# LaserLEDController.net
KiCad netlist of a schematic drawn in Altium Designer
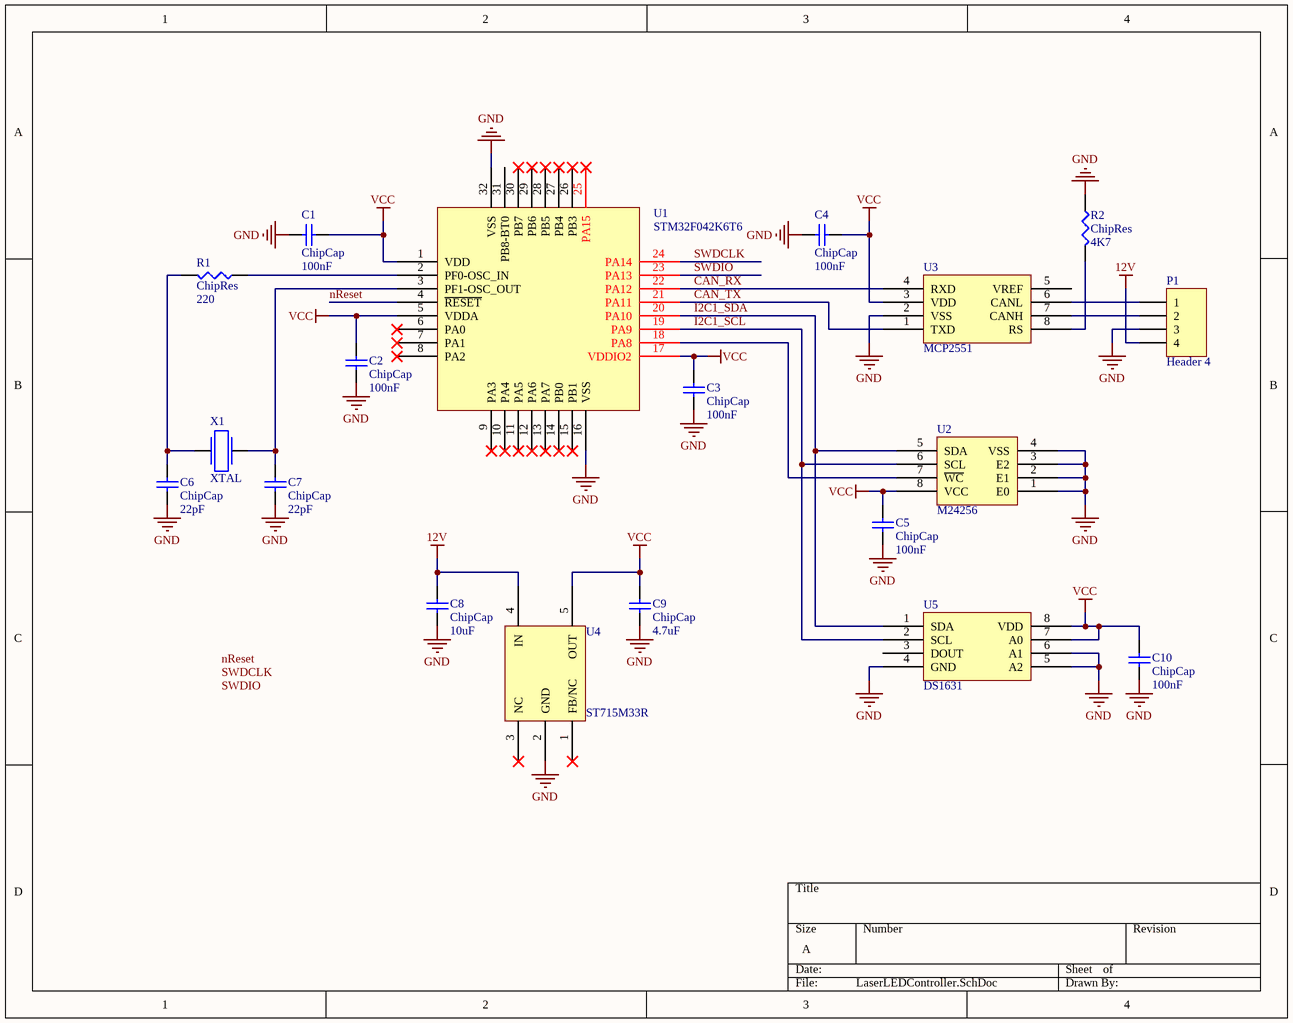
[diagram p0: LaserLEDController.SchDoc]

(export (version "E")
  (design (tool "Eeschema 10.0.6"))
  (components
    (comp (ref "C1")
      (value "ChipCap")
      (footprint "CAP0603")
      (description "Capacitor")
      (fields (field (name "ALTIUM_VALUE") "100nF") (field (name "PUBLISHER") "Altium Limited"))
      (libsource (lib "Common Devices") (part "ChipCap"))
    )
    (comp (ref "C2")
      (value "ChipCap")
      (footprint "CAP0603")
      (description "Capacitor")
      (fields (field (name "ALTIUM_VALUE") "100nF") (field (name "PUBLISHER") "Altium Limited"))
      (libsource (lib "Common Devices") (part "ChipCap"))
    )
    (comp (ref "C3")
      (value "ChipCap")
      (footprint "CAP0603")
      (description "Capacitor")
      (fields (field (name "ALTIUM_VALUE") "100nF") (field (name "PUBLISHER") "Altium Limited"))
      (libsource (lib "Common Devices") (part "ChipCap"))
    )
    (comp (ref "C4")
      (value "ChipCap")
      (footprint "CAP0603")
      (description "Capacitor")
      (fields (field (name "ALTIUM_VALUE") "100nF") (field (name "PUBLISHER") "Altium Limited"))
      (libsource (lib "Common Devices") (part "ChipCap"))
    )
    (comp (ref "C5")
      (value "ChipCap")
      (footprint "CAP0603")
      (description "Capacitor")
      (fields (field (name "ALTIUM_VALUE") "100nF") (field (name "PUBLISHER") "Altium Limited"))
      (libsource (lib "Common Devices") (part "ChipCap"))
    )
    (comp (ref "C6")
      (value "ChipCap")
      (footprint "CAP0603")
      (description "Capacitor")
      (fields (field (name "ALTIUM_VALUE") "22pF") (field (name "PUBLISHER") "Altium Limited"))
      (libsource (lib "Common Devices") (part "ChipCap"))
    )
    (comp (ref "C7")
      (value "ChipCap")
      (footprint "CAP0603")
      (description "Capacitor")
      (fields (field (name "ALTIUM_VALUE") "22pF") (field (name "PUBLISHER") "Altium Limited"))
      (libsource (lib "Common Devices") (part "ChipCap"))
    )
    (comp (ref "C8")
      (value "ChipCap")
      (footprint "CAP0805")
      (description "Capacitor")
      (fields (field (name "ALTIUM_VALUE") "10uF") (field (name "PUBLISHER") "Altium Limited"))
      (libsource (lib "Common Devices") (part "ChipCap"))
    )
    (comp (ref "C9")
      (value "ChipCap")
      (footprint "CAP0805")
      (description "Capacitor")
      (fields (field (name "ALTIUM_VALUE") "4.7uF") (field (name "PUBLISHER") "Altium Limited"))
      (libsource (lib "Common Devices") (part "ChipCap"))
    )
    (comp (ref "C10")
      (value "ChipCap")
      (footprint "CAP0603")
      (description "Capacitor")
      (fields (field (name "ALTIUM_VALUE") "100nF") (field (name "PUBLISHER") "Altium Limited"))
      (libsource (lib "Common Devices") (part "ChipCap"))
    )
    (comp (ref "P1")
      (value "Header 4")
      (footprint "HDR1X4")
      (description "Header, 4-Pin")
      (fields (field (name "PUBLISHER") "Altium Limited"))
      (libsource (lib "Miscellaneous Connectors") (part "Header 4"))
    )
    (comp (ref "R1")
      (value "ChipRes")
      (footprint "RES0603")
      (description "Chip resistor")
      (fields (field (name "ALTIUM_VALUE") "220"))
      (libsource (lib "Common Devices") (part "ChipRes"))
    )
    (comp (ref "R2")
      (value "ChipRes")
      (footprint "RES0603")
      (description "Chip resistor")
      (fields (field (name "ALTIUM_VALUE") "4K7"))
      (libsource (lib "Common Devices") (part "ChipRes"))
    )
    (comp (ref "U1")
      (value "STM32F042K6T6")
      (footprint "LQFP32")
      (description "ARM Cortex-M0 Microcontroller")
      (libsource (lib "ST ARM32") (part "STM32F042K6T6"))
    )
    (comp (ref "U2")
      (value "M24256")
      (footprint "SOIC8")
      (description "256 Kbit I2C EEPROM")
      (libsource (lib "ST EEPROM") (part "M24256"))
    )
    (comp (ref "U3")
      (value "MCP2551")
      (footprint "SOIC8")
      (description "CAN Transceiver")
      (libsource (lib "Microchip CAN Transceiver") (part "MCP2551-I/SN"))
    )
    (comp (ref "U4")
      (value "ST715M33R")
      (footprint "SOT23-5")
      (description "High input voltage - 85 mA LDO linear regulator")
      (libsource (lib "Common Devices") (part "ST715M33R"))
    )
    (comp (ref "U5")
      (value "DS1631")
      (footprint "SOIC8")
      (description "High-Precision Digital  Thermometer and Thermostat")
      (libsource (lib "Maxim Termosensor") (part "DS1631"))
    )
    (comp (ref "X1")
      (value "XTAL")
      (footprint "ABM3 Ceramic Crystal")
      (description "Quartz crystall oscillator")
      (libsource (lib "Common Devices") (part "ABM3 Ceramic SMD Crystal"))
    )
  )
  (nets
    (net (code "1") (name "/CAN_RX") (class "Default")
      (node (ref "U1") (pin "22") (pinfunction "PA12_22") (pintype "passive"))
      (node (ref "U3") (pin "4") (pinfunction "RXD_4") (pintype "passive"))
    )
    (net (code "2") (name "/CAN_TX") (class "Default")
      (node (ref "U1") (pin "21") (pinfunction "PA11_21") (pintype "passive"))
      (node (ref "U3") (pin "1") (pinfunction "TXD_1") (pintype "passive"))
    )
    (net (code "3") (name "/I2C1_SCL") (class "Default")
      (node (ref "U1") (pin "19") (pinfunction "PA9_19") (pintype "passive"))
      (node (ref "U2") (pin "6") (pinfunction "SCL_6") (pintype "passive"))
      (node (ref "U5") (pin "2") (pinfunction "SCL_2") (pintype "passive"))
    )
    (net (code "4") (name "/I2C1_SDA") (class "Default")
      (node (ref "U1") (pin "20") (pinfunction "PA10_20") (pintype "passive"))
      (node (ref "U2") (pin "5") (pinfunction "SDA_5") (pintype "passive"))
      (node (ref "U5") (pin "1") (pinfunction "SDA_1") (pintype "passive"))
    )
    (net (code "5") (name "/SWDCLK") (class "Default")
      (node (ref "U1") (pin "24") (pinfunction "PA14_24") (pintype "passive"))
    )
    (net (code "6") (name "/SWDIO") (class "Default")
      (node (ref "U1") (pin "23") (pinfunction "PA13_23") (pintype "passive"))
    )
    (net (code "7") (name "/nReset") (class "Default")
      (node (ref "U1") (pin "4") (pinfunction "~{RESET}_4") (pintype "passive"))
    )
    (net (code "8") (name "12V") (class "Default")
      (node (ref "C8") (pin "2") (pinfunction "2_2") (pintype "passive"))
      (node (ref "P1") (pin "4") (pinfunction "4_4") (pintype "passive"))
      (node (ref "U4") (pin "4") (pinfunction "IN_4") (pintype "passive"))
    )
    (net (code "9") (name "GND") (class "Default")
      (node (ref "C1") (pin "1") (pinfunction "1_1") (pintype "passive"))
      (node (ref "C10") (pin "1") (pinfunction "1_1") (pintype "passive"))
      (node (ref "C2") (pin "1") (pinfunction "1_1") (pintype "passive"))
      (node (ref "C3") (pin "1") (pinfunction "1_1") (pintype "passive"))
      (node (ref "C4") (pin "2") (pinfunction "2_2") (pintype "passive"))
      (node (ref "C5") (pin "1") (pinfunction "1_1") (pintype "passive"))
      (node (ref "C6") (pin "1") (pinfunction "1_1") (pintype "passive"))
      (node (ref "C7") (pin "1") (pinfunction "1_1") (pintype "passive"))
      (node (ref "C8") (pin "1") (pinfunction "1_1") (pintype "passive"))
      (node (ref "C9") (pin "1") (pinfunction "1_1") (pintype "passive"))
      (node (ref "P1") (pin "3") (pinfunction "3_3") (pintype "passive"))
      (node (ref "R2") (pin "1") (pintype "passive"))
      (node (ref "U1") (pin "16") (pinfunction "VSS_16") (pintype "passive"))
      (node (ref "U1") (pin "32") (pinfunction "VSS_32") (pintype "passive"))
      (node (ref "U2") (pin "1") (pinfunction "E0_1") (pintype "passive"))
      (node (ref "U2") (pin "2") (pinfunction "E1_2") (pintype "passive"))
      (node (ref "U2") (pin "3") (pinfunction "E2_3") (pintype "passive"))
      (node (ref "U2") (pin "4") (pinfunction "VSS_4") (pintype "passive"))
      (node (ref "U3") (pin "2") (pinfunction "VSS_2") (pintype "passive"))
      (node (ref "U4") (pin "2") (pinfunction "GND_2") (pintype "passive"))
      (node (ref "U5") (pin "4") (pinfunction "GND_4") (pintype "passive"))
      (node (ref "U5") (pin "5") (pinfunction "A2_5") (pintype "passive"))
      (node (ref "U5") (pin "6") (pinfunction "A1_6") (pintype "passive"))
    )
    (net (code "10") (name "Net-(C6-Pad2)") (class "Default")
      (node (ref "C6") (pin "2") (pinfunction "2_2") (pintype "passive"))
      (node (ref "R1") (pin "2") (pintype "passive"))
      (node (ref "X1") (pin "1") (pinfunction "1_1") (pintype "passive"))
    )
    (net (code "11") (name "Net-(U1-PA8)") (class "Default")
      (node (ref "U1") (pin "18") (pinfunction "PA8_18") (pintype "passive"))
      (node (ref "U2") (pin "7") (pinfunction "~{WC}_7") (pintype "passive"))
    )
    (net (code "12") (name "Net-(U1-PF0-OSC_IN)") (class "Default")
      (node (ref "R1") (pin "1") (pintype "passive"))
      (node (ref "U1") (pin "2") (pinfunction "PF0-OSC_IN_2") (pintype "passive"))
    )
    (net (code "13") (name "Net-(U1-PF1-OSC_OUT)") (class "Default")
      (node (ref "C7") (pin "2") (pinfunction "2_2") (pintype "passive"))
      (node (ref "U1") (pin "3") (pinfunction "PF1-OSC_OUT_3") (pintype "passive"))
      (node (ref "X1") (pin "2") (pinfunction "2_2") (pintype "passive"))
    )
    (net (code "14") (name "Net-(U3-CANH)") (class "Default")
      (node (ref "P1") (pin "2") (pinfunction "2_2") (pintype "passive"))
      (node (ref "U3") (pin "7") (pinfunction "CANH_7") (pintype "passive"))
    )
    (net (code "15") (name "Net-(U3-CANL)") (class "Default")
      (node (ref "P1") (pin "1") (pinfunction "1_1") (pintype "passive"))
      (node (ref "U3") (pin "6") (pinfunction "CANL_6") (pintype "passive"))
    )
    (net (code "16") (name "Net-(U3-RS)") (class "Default")
      (node (ref "R2") (pin "2") (pintype "passive"))
      (node (ref "U3") (pin "8") (pinfunction "RS_8") (pintype "passive"))
    )
    (net (code "17") (name "VCC") (class "Default")
      (node (ref "C1") (pin "2") (pinfunction "2_2") (pintype "passive"))
      (node (ref "C10") (pin "2") (pinfunction "2_2") (pintype "passive"))
      (node (ref "C2") (pin "2") (pinfunction "2_2") (pintype "passive"))
      (node (ref "C3") (pin "2") (pinfunction "2_2") (pintype "passive"))
      (node (ref "C4") (pin "1") (pinfunction "1_1") (pintype "passive"))
      (node (ref "C5") (pin "2") (pinfunction "2_2") (pintype "passive"))
      (node (ref "C9") (pin "2") (pinfunction "2_2") (pintype "passive"))
      (node (ref "U1") (pin "1") (pinfunction "VDD_1") (pintype "passive"))
      (node (ref "U1") (pin "17") (pinfunction "VDDIO2_17") (pintype "passive"))
      (node (ref "U1") (pin "5") (pinfunction "VDDA_5") (pintype "passive"))
      (node (ref "U2") (pin "8") (pinfunction "VCC_8") (pintype "passive"))
      (node (ref "U3") (pin "3") (pinfunction "VDD_3") (pintype "passive"))
      (node (ref "U4") (pin "5") (pinfunction "OUT_5") (pintype "passive"))
      (node (ref "U5") (pin "7") (pinfunction "A0_7") (pintype "passive"))
      (node (ref "U5") (pin "8") (pinfunction "VDD_8") (pintype "passive"))
    )
    (net (code "18") (name "unconnected-(U1-PA0-Pad6)") (class "Default")
      (node (ref "U1") (pin "6") (pinfunction "PA0_6") (pintype "passive+no_connect"))
    )
    (net (code "19") (name "unconnected-(U1-PA1-Pad7)") (class "Default")
      (node (ref "U1") (pin "7") (pinfunction "PA1_7") (pintype "passive+no_connect"))
    )
    (net (code "20") (name "unconnected-(U1-PA2-Pad8)") (class "Default")
      (node (ref "U1") (pin "8") (pinfunction "PA2_8") (pintype "passive+no_connect"))
    )
    (net (code "21") (name "unconnected-(U1-PA3-Pad9)") (class "Default")
      (node (ref "U1") (pin "9") (pinfunction "PA3_9") (pintype "passive+no_connect"))
    )
    (net (code "22") (name "unconnected-(U1-PA4-Pad10)") (class "Default")
      (node (ref "U1") (pin "10") (pinfunction "PA4_10") (pintype "passive+no_connect"))
    )
    (net (code "23") (name "unconnected-(U1-PA5-Pad11)") (class "Default")
      (node (ref "U1") (pin "11") (pinfunction "PA5_11") (pintype "passive+no_connect"))
    )
    (net (code "24") (name "unconnected-(U1-PA6-Pad12)") (class "Default")
      (node (ref "U1") (pin "12") (pinfunction "PA6_12") (pintype "passive+no_connect"))
    )
    (net (code "25") (name "unconnected-(U1-PA7-Pad13)") (class "Default")
      (node (ref "U1") (pin "13") (pinfunction "PA7_13") (pintype "passive+no_connect"))
    )
    (net (code "26") (name "unconnected-(U1-PA15-Pad25)") (class "Default")
      (node (ref "U1") (pin "25") (pinfunction "PA15_25") (pintype "passive+no_connect"))
    )
    (net (code "27") (name "unconnected-(U1-PB0-Pad14)") (class "Default")
      (node (ref "U1") (pin "14") (pinfunction "PB0_14") (pintype "passive+no_connect"))
    )
    (net (code "28") (name "unconnected-(U1-PB1-Pad15)") (class "Default")
      (node (ref "U1") (pin "15") (pinfunction "PB1_15") (pintype "passive+no_connect"))
    )
    (net (code "29") (name "unconnected-(U1-PB3-Pad26)") (class "Default")
      (node (ref "U1") (pin "26") (pinfunction "PB3_26") (pintype "passive+no_connect"))
    )
    (net (code "30") (name "unconnected-(U1-PB4-Pad27)") (class "Default")
      (node (ref "U1") (pin "27") (pinfunction "PB4_27") (pintype "passive+no_connect"))
    )
    (net (code "31") (name "unconnected-(U1-PB5-Pad28)") (class "Default")
      (node (ref "U1") (pin "28") (pinfunction "PB5_28") (pintype "passive+no_connect"))
    )
    (net (code "32") (name "unconnected-(U1-PB6-Pad29)") (class "Default")
      (node (ref "U1") (pin "29") (pinfunction "PB6_29") (pintype "passive+no_connect"))
    )
    (net (code "33") (name "unconnected-(U1-PB7-Pad30)") (class "Default")
      (node (ref "U1") (pin "30") (pinfunction "PB7_30") (pintype "passive+no_connect"))
    )
    (net (code "34") (name "unconnected-(U1-PB8-BT0-Pad31)") (class "Default")
      (node (ref "U1") (pin "31") (pinfunction "PB8-BT0_31") (pintype "passive"))
    )
    (net (code "35") (name "unconnected-(U3-VREF-Pad5)") (class "Default")
      (node (ref "U3") (pin "5") (pinfunction "VREF_5") (pintype "passive"))
    )
    (net (code "36") (name "unconnected-(U4-FB{slash}NC-Pad1)") (class "Default")
      (node (ref "U4") (pin "1") (pinfunction "FB/NC_1") (pintype "passive+no_connect"))
    )
    (net (code "37") (name "unconnected-(U4-NC-Pad3)") (class "Default")
      (node (ref "U4") (pin "3") (pinfunction "NC_3") (pintype "passive+no_connect"))
    )
    (net (code "38") (name "unconnected-(U5-DOUT-Pad3)") (class "Default")
      (node (ref "U5") (pin "3") (pinfunction "DOUT_3") (pintype "passive"))
    )
  )
)
